# step_down.net
KiCad netlist of a schematic drawn in EAGLE
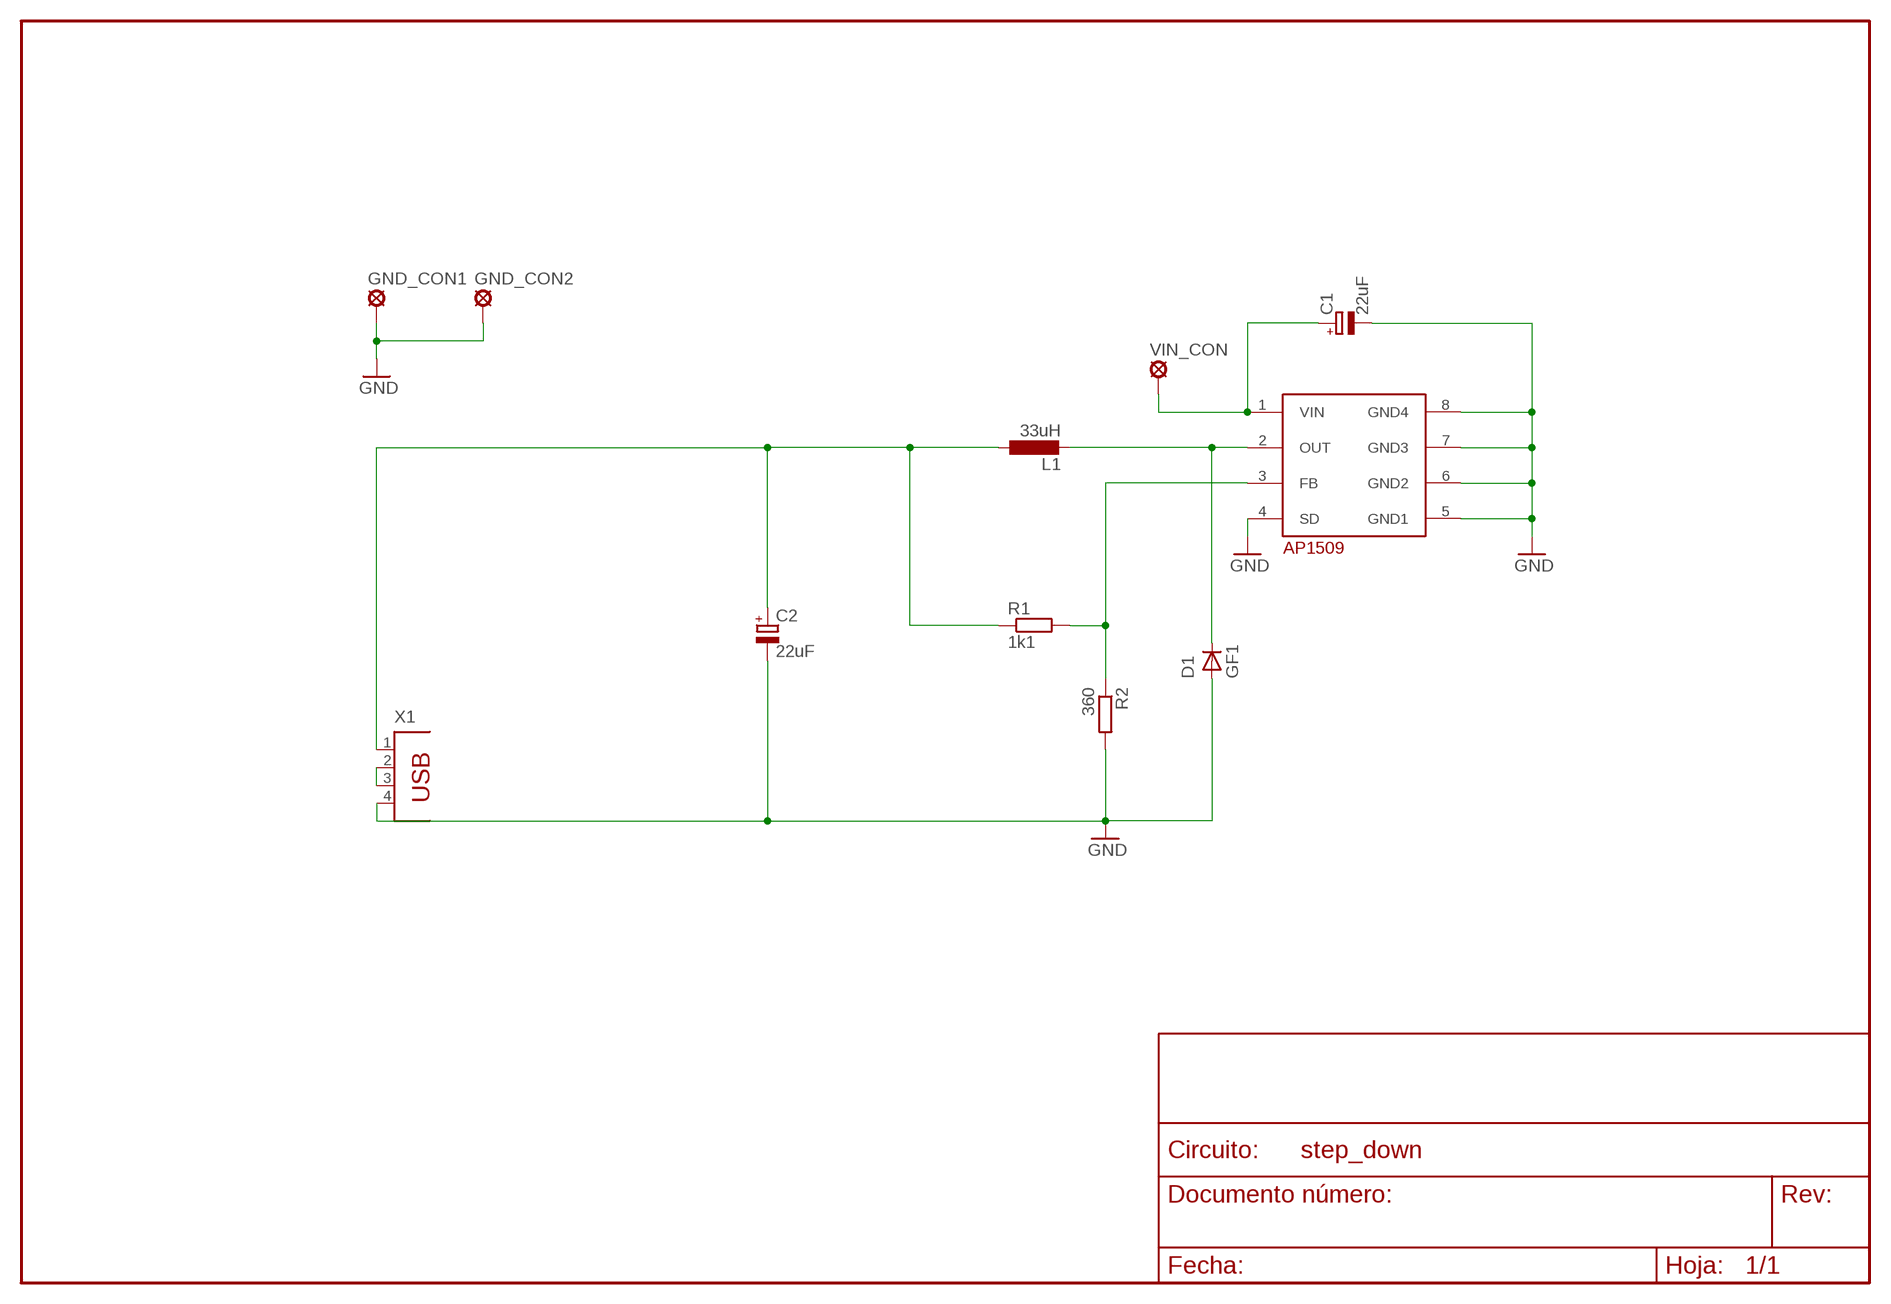
[diagram p0: schematic, sheet 1]

(export (version "E")
  (design (tool "Eeschema 10.0.6"))
  (components
    (comp (ref "C1")
      (value "22uF")
      (footprint "eagle-import:CT7343")
      (libsource (lib "eagle-import") (part "CPOL-EUCT7343"))
    )
    (comp (ref "C2")
      (value "22uF")
      (footprint "eagle-import:CT3216")
      (libsource (lib "eagle-import") (part "CPOL-EUCT3216"))
    )
    (comp (ref "D1")
      (value "GF1")
      (footprint "eagle-import:SMA-DO214AC")
      (fields (field (name "SPICEPREFIX") "D"))
      (libsource (lib "eagle-import") (part "GF1"))
    )
    (comp (ref "GND_CON1")
      (value "SE14")
      (footprint "eagle-import:SE14")
      (libsource (lib "eagle-import") (part "SE14"))
    )
    (comp (ref "GND_CON2")
      (value "SE14")
      (footprint "eagle-import:SE14")
      (libsource (lib "eagle-import") (part "SE14"))
    )
    (comp (ref "L1")
      (value "33uH")
      (footprint "eagle-import:L8051")
      (libsource (lib "eagle-import") (part "SRN6045TAL"))
    )
    (comp (ref "R1")
      (value "1k1")
      (footprint "eagle-import:M3216")
      (libsource (lib "eagle-import") (part "R-EU_M3216"))
    )
    (comp (ref "R2")
      (value "360")
      (footprint "eagle-import:M3216")
      (libsource (lib "eagle-import") (part "R-EU_M3216"))
    )
    (comp (ref "U1")
      (value "AP1509S")
      (footprint "eagle-import:SOIC8")
      (libsource (lib "eagle-import") (part "AP1509S"))
    )
    (comp (ref "VIN_CON")
      (value "SE14")
      (footprint "eagle-import:SE14")
      (libsource (lib "eagle-import") (part "SE14"))
    )
    (comp (ref "X1")
      (value "PN87520")
      (footprint "eagle-import:PN87520")
      (libsource (lib "eagle-import") (part "PN87520"))
    )
  )
  (nets
    (net (code "1") (name "GND") (class "Default")
      (node (ref "C1") (pin "-") (pinfunction "-_-") (pintype "passive"))
      (node (ref "C2") (pin "-") (pinfunction "-_-") (pintype "passive"))
      (node (ref "D1") (pin "A") (pinfunction "A_A") (pintype "passive"))
      (node (ref "GND_CON1") (pin "MP") (pinfunction "MP_MP") (pintype "passive"))
      (node (ref "GND_CON2") (pin "MP") (pinfunction "MP_MP") (pintype "passive"))
      (node (ref "R2") (pin "2") (pinfunction "2_2") (pintype "passive"))
      (node (ref "U1") (pin "4") (pinfunction "SD_4") (pintype "passive"))
      (node (ref "U1") (pin "5") (pinfunction "GND1_5") (pintype "power_in"))
      (node (ref "U1") (pin "6") (pinfunction "GND2_6") (pintype "power_in"))
      (node (ref "U1") (pin "7") (pinfunction "GND3_7") (pintype "power_in"))
      (node (ref "U1") (pin "8") (pinfunction "GND4_8") (pintype "power_in"))
      (node (ref "X1") (pin "4") (pinfunction "4_4") (pintype "passive"))
    )
    (net (code "2") (name "Net-(C2-Pad+)") (class "Default")
      (node (ref "C2") (pin "+") (pinfunction "+_+") (pintype "passive"))
      (node (ref "L1") (pin "1") (pinfunction "1_1") (pintype "passive"))
      (node (ref "R1") (pin "1") (pinfunction "1_1") (pintype "passive"))
      (node (ref "X1") (pin "1") (pinfunction "1_1") (pintype "passive"))
    )
    (net (code "3") (name "Net-(D1-C)") (class "Default")
      (node (ref "D1") (pin "K") (pinfunction "C_K") (pintype "passive"))
      (node (ref "L1") (pin "2") (pinfunction "2_2") (pintype "passive"))
      (node (ref "U1") (pin "2") (pinfunction "OUT_2") (pintype "passive"))
    )
    (net (code "4") (name "Net-(U1-FB)") (class "Default")
      (node (ref "R1") (pin "2") (pinfunction "2_2") (pintype "passive"))
      (node (ref "R2") (pin "1") (pinfunction "1_1") (pintype "passive"))
      (node (ref "U1") (pin "3") (pinfunction "FB_3") (pintype "passive"))
    )
    (net (code "5") (name "Net-(U1-VIN)") (class "Default")
      (node (ref "C1") (pin "+") (pinfunction "+_+") (pintype "passive"))
      (node (ref "U1") (pin "1") (pinfunction "VIN_1") (pintype "power_in"))
      (node (ref "VIN_CON") (pin "MP") (pinfunction "MP_MP") (pintype "passive"))
    )
    (net (code "6") (name "Net-(X1-Pad2)") (class "Default")
      (node (ref "X1") (pin "2") (pinfunction "2_2") (pintype "passive"))
      (node (ref "X1") (pin "3") (pinfunction "3_3") (pintype "passive"))
    )
  )
)
